# BatteryCombinerControlBoard.net
KiCad netlist of a schematic drawn in EAGLE
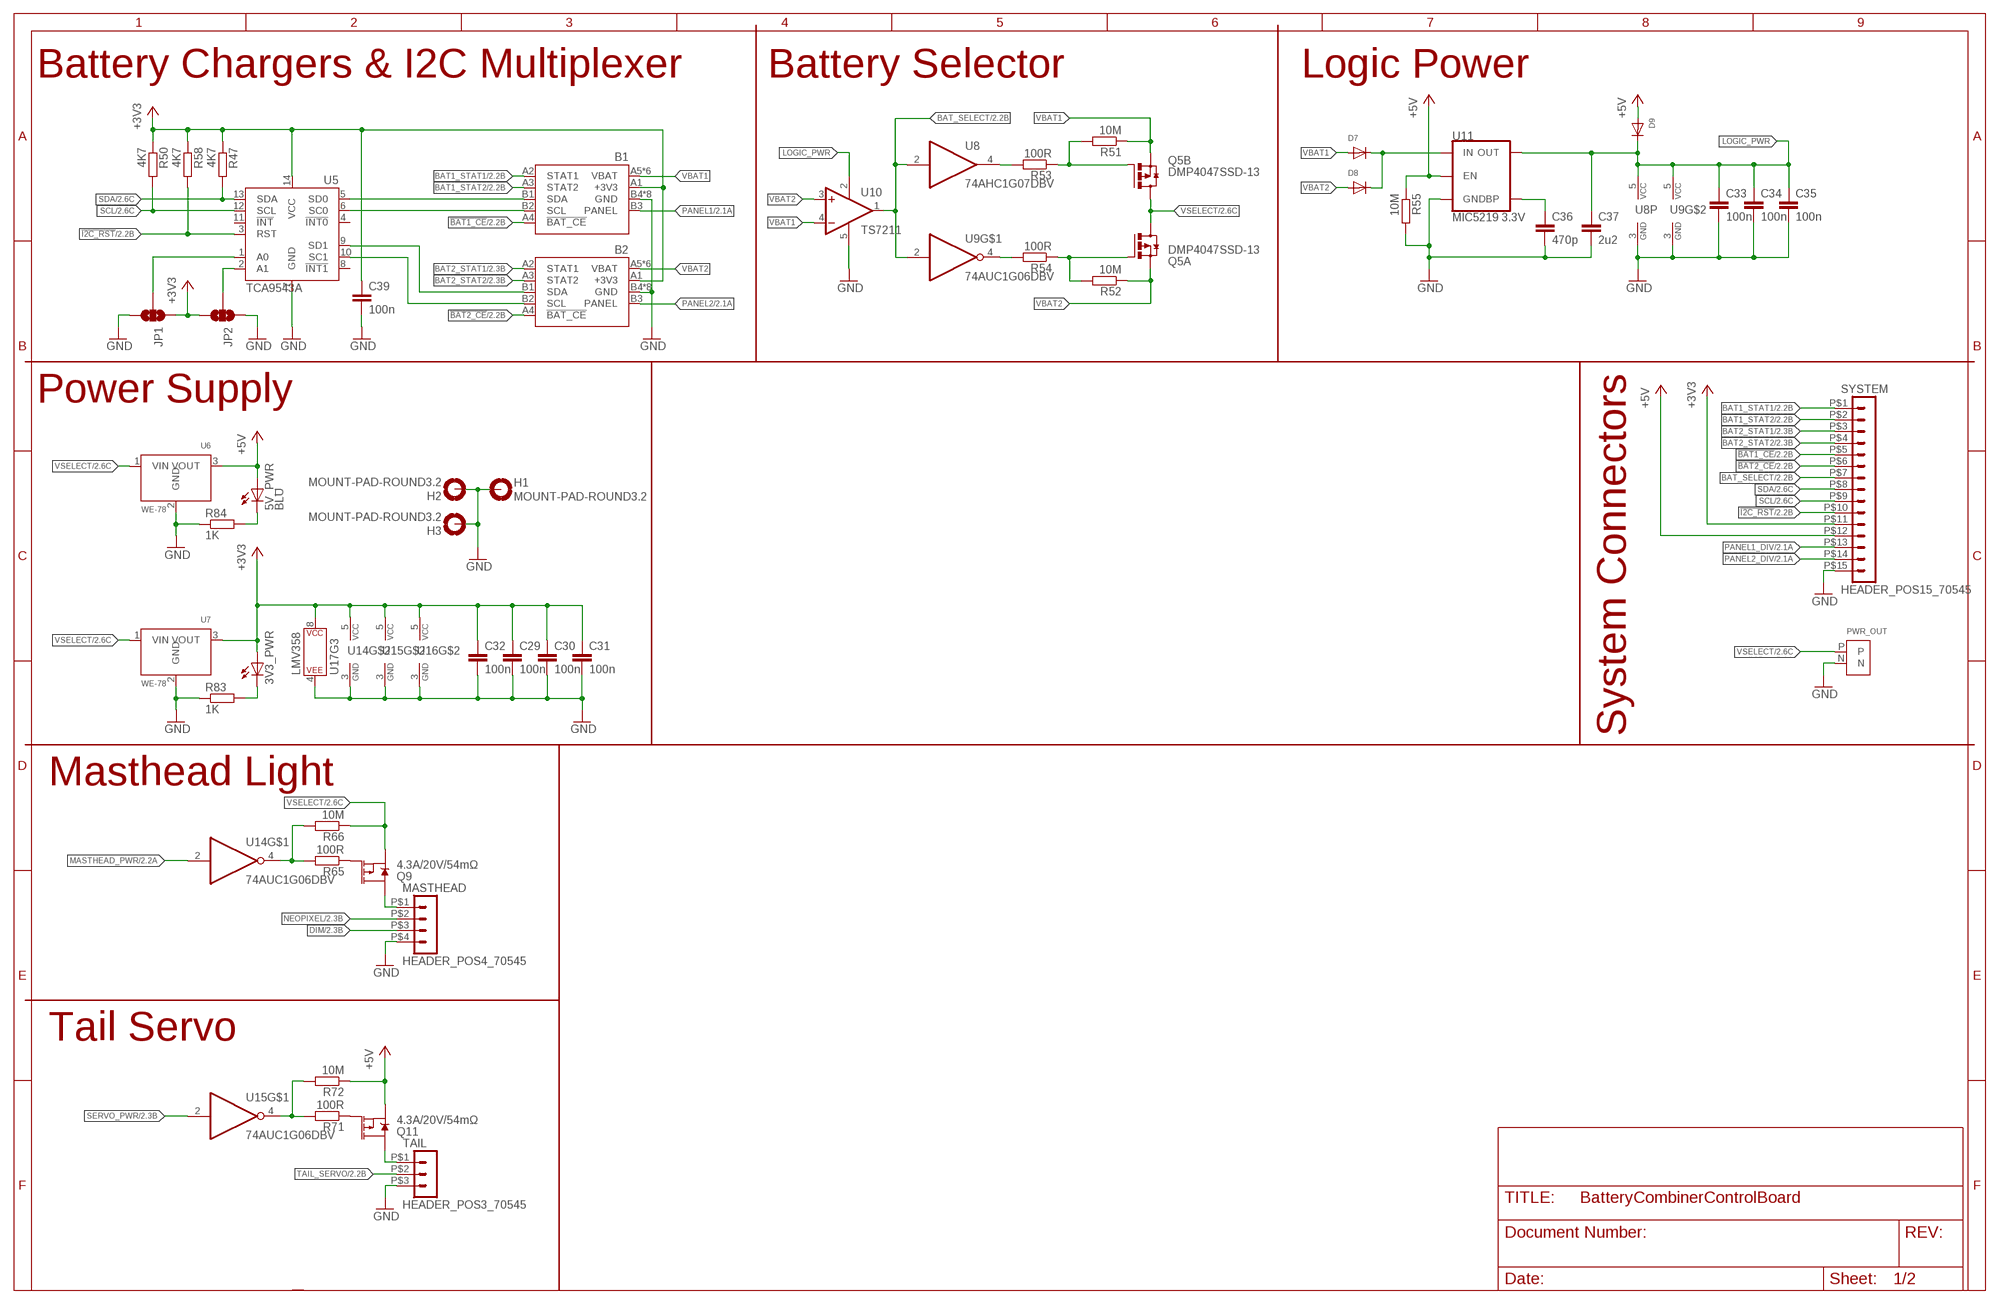
[diagram p0: schematic, sheet 1]
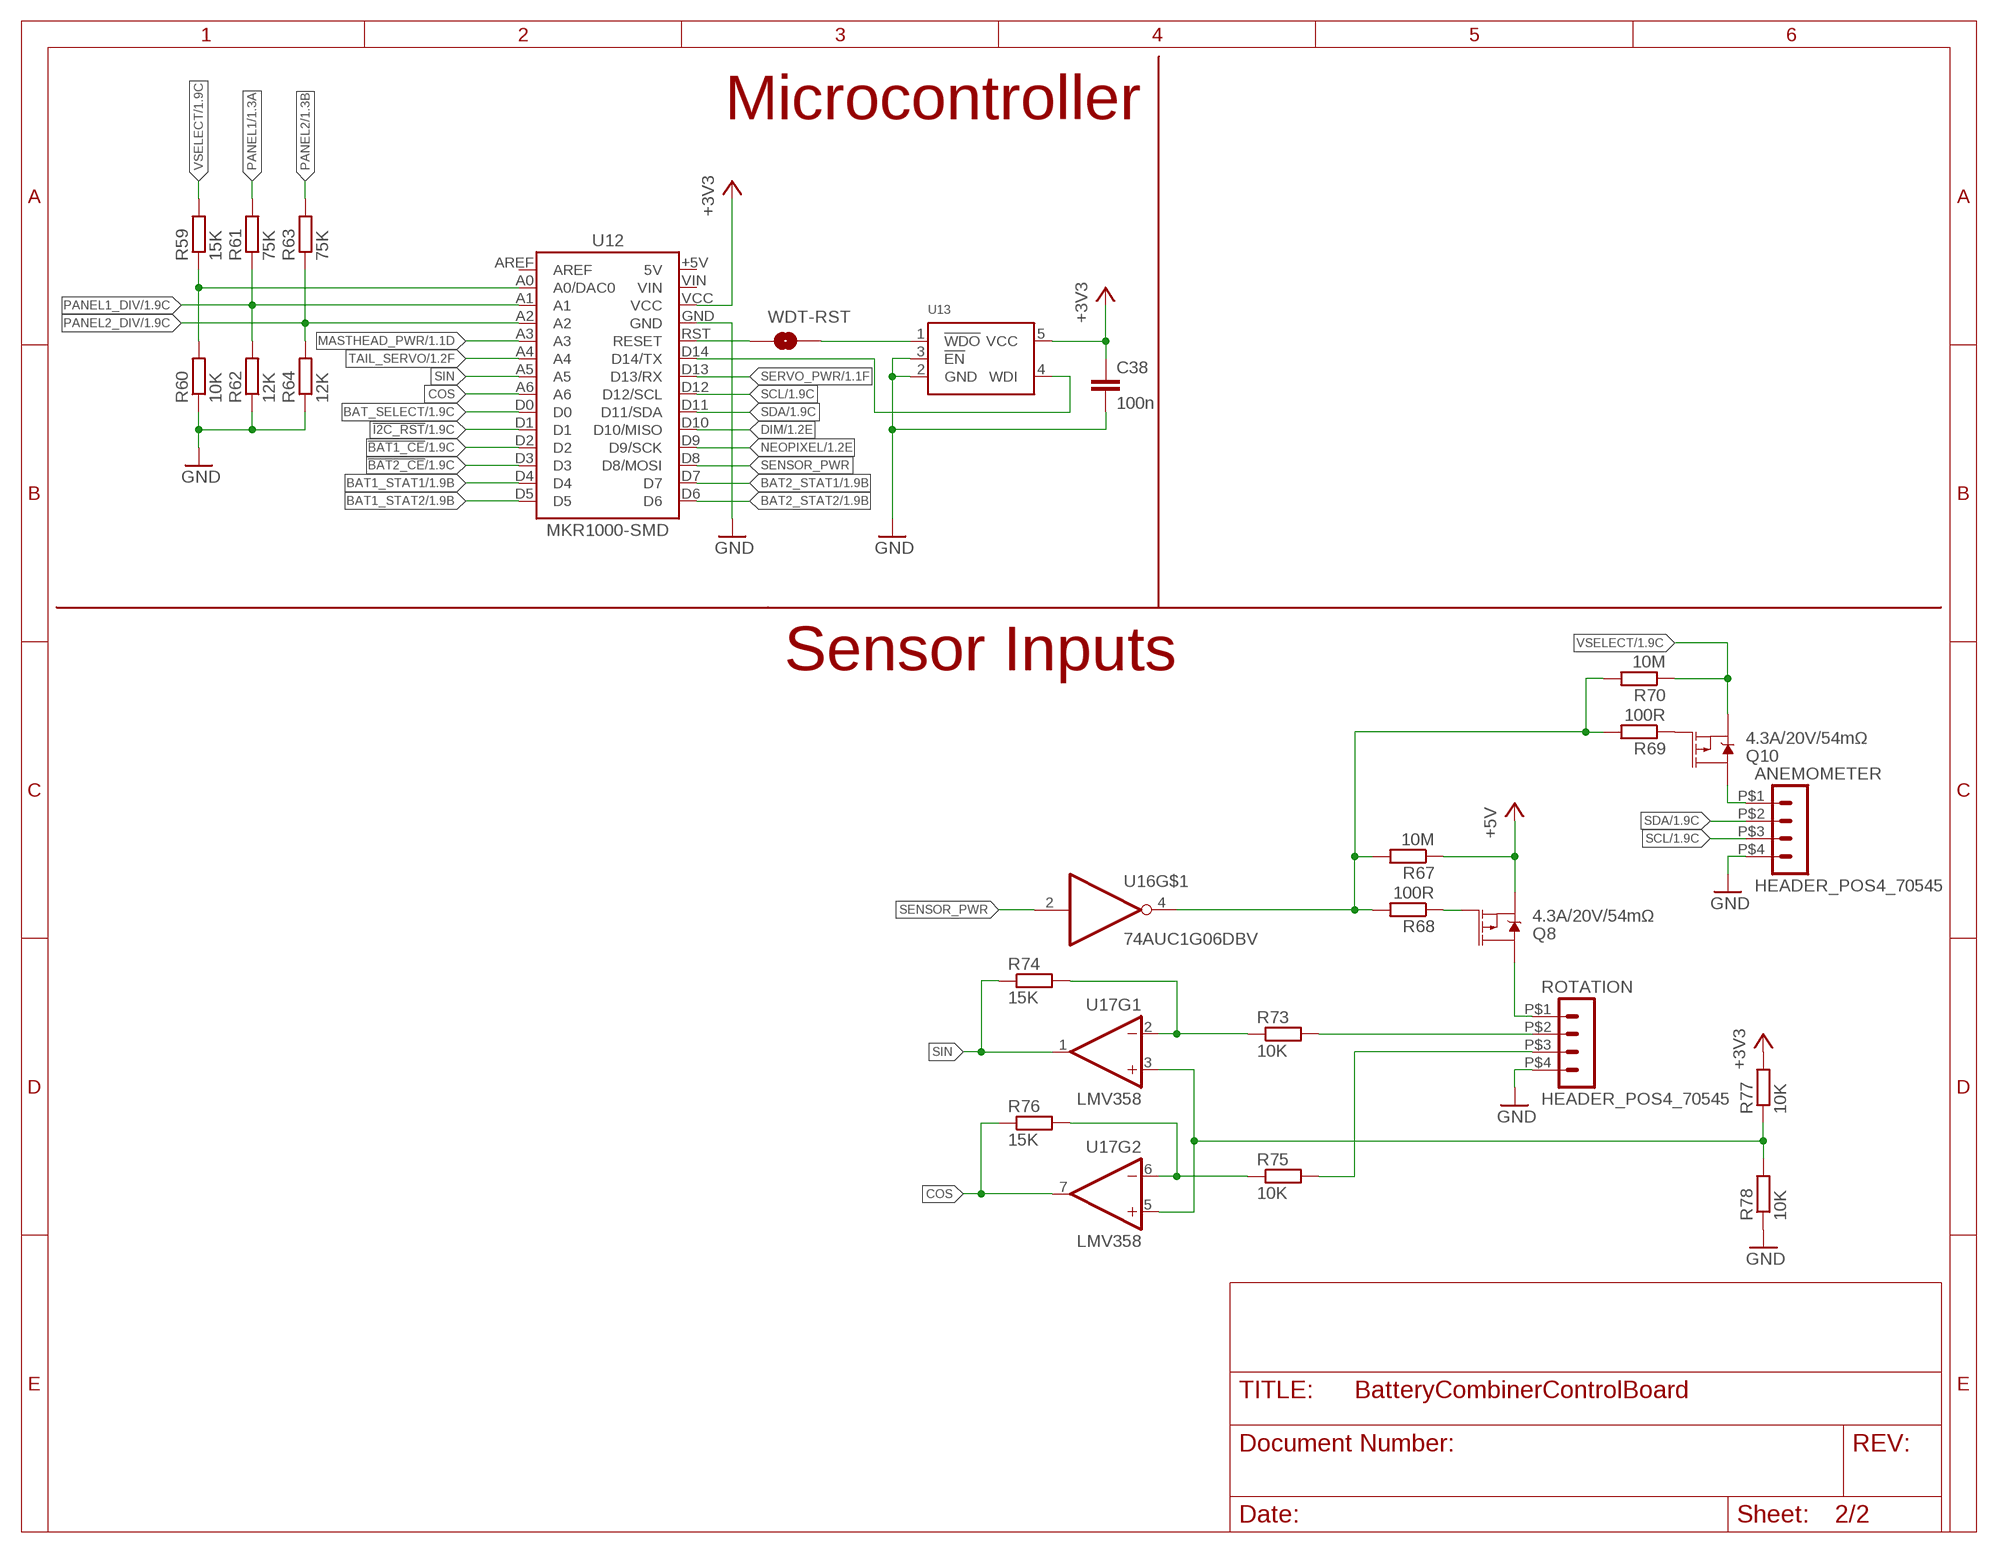
[diagram p1: schematic, sheet 2]

(export (version "E")
  (design (tool "Eeschema 10.0.6"))
  (components
    (comp (ref "ANEMOMETER")
      (value "HEADER_POS4_70545")
      (footprint "eagle-import:70545-POS4")
      (libsource (lib "eagle-import") (part "HEADER_POS4_?70545"))
    )
    (comp (ref "C38")
      (value "100n")
      (footprint "eagle-import:C0603")
      (libsource (lib "eagle-import") (part "C-EUC0603"))
    )
    (comp (ref "Q8")
      (value "4.3A/20V/54mΩ")
      (footprint "eagle-import:SOT23-3")
      (libsource (lib "eagle-import") (part "MOSFET_PCH-IRLML2244"))
    )
    (comp (ref "Q10")
      (value "4.3A/20V/54mΩ")
      (footprint "eagle-import:SOT23-3")
      (libsource (lib "eagle-import") (part "MOSFET_PCH-IRLML2244"))
    )
    (comp (ref "R59")
      (value "15K")
      (footprint "eagle-import:R0603")
      (libsource (lib "eagle-import") (part "R-EU_R0603"))
    )
    (comp (ref "R60")
      (value "10K")
      (footprint "eagle-import:R0603")
      (libsource (lib "eagle-import") (part "R-EU_R0603"))
    )
    (comp (ref "R61")
      (value "75K")
      (footprint "eagle-import:R0603")
      (libsource (lib "eagle-import") (part "R-EU_R0603"))
    )
    (comp (ref "R62")
      (value "12K")
      (footprint "eagle-import:R0603")
      (libsource (lib "eagle-import") (part "R-EU_R0603"))
    )
    (comp (ref "R63")
      (value "75K")
      (footprint "eagle-import:R0603")
      (libsource (lib "eagle-import") (part "R-EU_R0603"))
    )
    (comp (ref "R64")
      (value "12K")
      (footprint "eagle-import:R0603")
      (libsource (lib "eagle-import") (part "R-EU_R0603"))
    )
    (comp (ref "R67")
      (value "10M")
      (footprint "eagle-import:R0603")
      (libsource (lib "eagle-import") (part "R-EU_R0603"))
    )
    (comp (ref "R68")
      (value "100R")
      (footprint "eagle-import:R0603")
      (libsource (lib "eagle-import") (part "R-EU_R0603"))
    )
    (comp (ref "R69")
      (value "100R")
      (footprint "eagle-import:R0603")
      (libsource (lib "eagle-import") (part "R-EU_R0603"))
    )
    (comp (ref "R70")
      (value "10M")
      (footprint "eagle-import:R0603")
      (libsource (lib "eagle-import") (part "R-EU_R0603"))
    )
    (comp (ref "R73")
      (value "10K")
      (footprint "eagle-import:R0603")
      (libsource (lib "eagle-import") (part "R-EU_R0603"))
    )
    (comp (ref "R74")
      (value "15K")
      (footprint "eagle-import:R0603")
      (libsource (lib "eagle-import") (part "R-EU_R0603"))
    )
    (comp (ref "R75")
      (value "10K")
      (footprint "eagle-import:R0603")
      (libsource (lib "eagle-import") (part "R-EU_R0603"))
    )
    (comp (ref "R76")
      (value "15K")
      (footprint "eagle-import:R0603")
      (libsource (lib "eagle-import") (part "R-EU_R0603"))
    )
    (comp (ref "R77")
      (value "10K")
      (footprint "eagle-import:R0603")
      (libsource (lib "eagle-import") (part "R-EU_R0603"))
    )
    (comp (ref "R78")
      (value "10K")
      (footprint "eagle-import:R0603")
      (libsource (lib "eagle-import") (part "R-EU_R0603"))
    )
    (comp (ref "ROTATION")
      (value "HEADER_POS4_70545")
      (footprint "eagle-import:70545-POS4")
      (libsource (lib "eagle-import") (part "HEADER_POS4_?70545"))
    )
    (comp (ref "U12")
      (value "MKR1000-SMD")
      (footprint "eagle-import:MKR1000-SMD")
      (libsource (lib "eagle-import") (part "MKR1000-SMD"))
    )
    (comp (ref "U13")
      (value "STWD100")
      (footprint "eagle-import:DBV-R-PDSO-G5")
      (libsource (lib "eagle-import") (part "STWD100"))
    )
    (comp (ref "U16")
      (value "74AUC1G06DBV")
      (footprint "eagle-import:SOT23-5")
      (libsource (lib "eagle-import") (part "741G06DBVAUC"))
    )
    (comp (ref "U17")
      (value "LMV358")
      (footprint "eagle-import:SO08")
      (libsource (lib "eagle-import") (part "LMV358SOIC"))
    )
    (comp (ref "WDT-RST")
      (value "JUMPER-SMT_2_NO_SILK")
      (footprint "eagle-import:SMT-JUMPER_2_NO_SILK")
      (libsource (lib "eagle-import") (part "JUMPER-SMT_2_NO_SILK"))
    )
    (comp (ref "3V3_PWR")
      (value "GRN")
      (footprint "eagle-import:CHIP-LED0603")
      (libsource (lib "eagle-import") (part "LEDCHIP-LED0603"))
    )
    (comp (ref "5V_PWR")
      (value "BLU")
      (footprint "eagle-import:CHIP-LED0603")
      (libsource (lib "eagle-import") (part "LEDCHIP-LED0603"))
    )
    (comp (ref "B1")
      (value "MPPTCHARGER")
      (footprint "eagle-import:MPPTCHARGER")
      (libsource (lib "eagle-import") (part "MPPTCHARGER"))
    )
    (comp (ref "B2")
      (value "MPPTCHARGER")
      (footprint "eagle-import:MPPTCHARGER")
      (libsource (lib "eagle-import") (part "MPPTCHARGER"))
    )
    (comp (ref "C29")
      (value "100n")
      (footprint "eagle-import:C0603")
      (libsource (lib "eagle-import") (part "C-EUC0603"))
    )
    (comp (ref "C30")
      (value "100n")
      (footprint "eagle-import:C0603")
      (libsource (lib "eagle-import") (part "C-EUC0603"))
    )
    (comp (ref "C31")
      (value "100n")
      (footprint "eagle-import:C0603")
      (libsource (lib "eagle-import") (part "C-EUC0603"))
    )
    (comp (ref "C32")
      (value "100n")
      (footprint "eagle-import:C0603")
      (libsource (lib "eagle-import") (part "C-EUC0603"))
    )
    (comp (ref "C33")
      (value "100n")
      (footprint "eagle-import:C0603")
      (libsource (lib "eagle-import") (part "C-EUC0603"))
    )
    (comp (ref "C34")
      (value "100n")
      (footprint "eagle-import:C0603")
      (libsource (lib "eagle-import") (part "C-EUC0603"))
    )
    (comp (ref "C35")
      (value "100n")
      (footprint "eagle-import:C0603")
      (libsource (lib "eagle-import") (part "C-EUC0603"))
    )
    (comp (ref "C36")
      (value "470p")
      (footprint "eagle-import:C0603")
      (libsource (lib "eagle-import") (part "C-EUC0603"))
    )
    (comp (ref "C37")
      (value "2u2")
      (footprint "eagle-import:C0603")
      (libsource (lib "eagle-import") (part "C-EUC0603"))
    )
    (comp (ref "C39")
      (value "100n")
      (footprint "eagle-import:C0603")
      (libsource (lib "eagle-import") (part "C-EUC0603"))
    )
    (comp (ref "D7")
      (value "DIODESOD-123")
      (footprint "eagle-import:SOD-123")
      (libsource (lib "eagle-import") (part "DIODESOD-123"))
    )
    (comp (ref "D8")
      (value "DIODESOD-123")
      (footprint "eagle-import:SOD-123")
      (libsource (lib "eagle-import") (part "DIODESOD-123"))
    )
    (comp (ref "D9")
      (value "DIODESOD-123")
      (footprint "eagle-import:SOD-123")
      (libsource (lib "eagle-import") (part "DIODESOD-123"))
    )
    (comp (ref "H1")
      (value "MOUNT-PAD-ROUND3.2")
      (footprint "eagle-import:3,2-PAD")
      (libsource (lib "eagle-import") (part "MOUNT-PAD-ROUND3.2"))
    )
    (comp (ref "H2")
      (value "MOUNT-PAD-ROUND3.2")
      (footprint "eagle-import:3,2-PAD")
      (libsource (lib "eagle-import") (part "MOUNT-PAD-ROUND3.2"))
    )
    (comp (ref "H3")
      (value "MOUNT-PAD-ROUND3.2")
      (footprint "eagle-import:3,2-PAD")
      (libsource (lib "eagle-import") (part "MOUNT-PAD-ROUND3.2"))
    )
    (comp (ref "JP1")
      (value "JUMPER-SMT_3_NO_SILK")
      (footprint "eagle-import:SMT-JUMPER_3_NO_SILK")
      (libsource (lib "eagle-import") (part "JUMPER-SMT_3_NO_SILK"))
    )
    (comp (ref "JP2")
      (value "JUMPER-SMT_3_NO_SILK")
      (footprint "eagle-import:SMT-JUMPER_3_NO_SILK")
      (libsource (lib "eagle-import") (part "JUMPER-SMT_3_NO_SILK"))
    )
    (comp (ref "MASTHEAD")
      (value "HEADER_POS4_70545")
      (footprint "eagle-import:70545-POS4")
      (libsource (lib "eagle-import") (part "HEADER_POS4_?70545"))
    )
    (comp (ref "PWR_OUT")
      (value "PWR")
      (footprint "eagle-import:JST-XH2-THRUHOLE")
      (libsource (lib "eagle-import") (part "PWR"))
    )
    (comp (ref "Q5")
      (value "DMP4047SSD-13")
      (footprint "eagle-import:SO08")
      (libsource (lib "eagle-import") (part "DMP4047SSD-13"))
    )
    (comp (ref "Q9")
      (value "4.3A/20V/54mΩ")
      (footprint "eagle-import:SOT23-3")
      (libsource (lib "eagle-import") (part "MOSFET_PCH-IRLML2244"))
    )
    (comp (ref "Q11")
      (value "4.3A/20V/54mΩ")
      (footprint "eagle-import:SOT23-3")
      (libsource (lib "eagle-import") (part "MOSFET_PCH-IRLML2244"))
    )
    (comp (ref "R47")
      (value "4K7")
      (footprint "eagle-import:R0603")
      (libsource (lib "eagle-import") (part "R-EU_R0603"))
    )
    (comp (ref "R50")
      (value "4K7")
      (footprint "eagle-import:R0603")
      (libsource (lib "eagle-import") (part "R-EU_R0603"))
    )
    (comp (ref "R51")
      (value "10M")
      (footprint "eagle-import:R0603")
      (libsource (lib "eagle-import") (part "R-EU_R0603"))
    )
    (comp (ref "R52")
      (value "10M")
      (footprint "eagle-import:R0603")
      (libsource (lib "eagle-import") (part "R-EU_R0603"))
    )
    (comp (ref "R53")
      (value "100R")
      (footprint "eagle-import:R0603")
      (libsource (lib "eagle-import") (part "R-EU_R0603"))
    )
    (comp (ref "R54")
      (value "100R")
      (footprint "eagle-import:R0603")
      (libsource (lib "eagle-import") (part "R-EU_R0603"))
    )
    (comp (ref "R55")
      (value "10M")
      (footprint "eagle-import:R0603")
      (libsource (lib "eagle-import") (part "R-EU_R0603"))
    )
    (comp (ref "R58")
      (value "4K7")
      (footprint "eagle-import:R0603")
      (libsource (lib "eagle-import") (part "R-EU_R0603"))
    )
    (comp (ref "R65")
      (value "100R")
      (footprint "eagle-import:R0603")
      (libsource (lib "eagle-import") (part "R-EU_R0603"))
    )
    (comp (ref "R66")
      (value "10M")
      (footprint "eagle-import:R0603")
      (libsource (lib "eagle-import") (part "R-EU_R0603"))
    )
    (comp (ref "R71")
      (value "100R")
      (footprint "eagle-import:R0603")
      (libsource (lib "eagle-import") (part "R-EU_R0603"))
    )
    (comp (ref "R72")
      (value "10M")
      (footprint "eagle-import:R0603")
      (libsource (lib "eagle-import") (part "R-EU_R0603"))
    )
    (comp (ref "R83")
      (value "1K")
      (footprint "eagle-import:R0603")
      (libsource (lib "eagle-import") (part "R-EU_R0603"))
    )
    (comp (ref "R84")
      (value "1K")
      (footprint "eagle-import:R0603")
      (libsource (lib "eagle-import") (part "R-EU_R0603"))
    )
    (comp (ref "SYSTEM")
      (value "HEADER_POS15_70545")
      (footprint "eagle-import:70545-POS15")
      (libsource (lib "eagle-import") (part "HEADER_POS15_?70545"))
    )
    (comp (ref "TAIL")
      (value "HEADER_POS3_70545")
      (footprint "eagle-import:70545-POS3")
      (libsource (lib "eagle-import") (part "HEADER_POS3_?70545"))
    )
    (comp (ref "U5")
      (value "TCA9543A")
      (footprint "eagle-import:SO-14")
      (libsource (lib "eagle-import") (part "TCA9543A"))
    )
    (comp (ref "U6")
      (value "WE-78")
      (footprint "eagle-import:WE-78")
      (libsource (lib "eagle-import") (part "WE-78"))
    )
    (comp (ref "U7")
      (value "WE-78")
      (footprint "eagle-import:WE-78")
      (libsource (lib "eagle-import") (part "WE-78"))
    )
    (comp (ref "U8")
      (value "74AHC1G07DBV")
      (footprint "eagle-import:SOT23-5")
      (libsource (lib "eagle-import") (part "741G07DBVAHC"))
    )
    (comp (ref "U9")
      (value "74AUC1G06DBV")
      (footprint "eagle-import:SOT23-5")
      (libsource (lib "eagle-import") (part "741G06DBVAUC"))
    )
    (comp (ref "U10")
      (value "TS7211")
      (footprint "eagle-import:DBV-R-PDSO-G5")
      (libsource (lib "eagle-import") (part "TS7211"))
    )
    (comp (ref "U11")
      (value "MIC5219 3.3V")
      (footprint "eagle-import:SOT23-5")
      (libsource (lib "eagle-import") (part "V_REG_MIC52193.3V"))
    )
    (comp (ref "U14")
      (value "74AUC1G06DBV")
      (footprint "eagle-import:SOT23-5")
      (libsource (lib "eagle-import") (part "741G06DBVAUC"))
    )
    (comp (ref "U15")
      (value "74AUC1G06DBV")
      (footprint "eagle-import:SOT23-5")
      (libsource (lib "eagle-import") (part "741G06DBVAUC"))
    )
  )
  (nets
    (net (code "1") (name "+3V3") (class "Default")
      (node (ref "3V3_PWR") (pin "A") (pinfunction "A_A") (pintype "passive"))
      (node (ref "B1") (pin "A1") (pinfunction "+3V3_A1") (pintype "bidirectional"))
      (node (ref "B2") (pin "A1") (pinfunction "+3V3_A1") (pintype "bidirectional"))
      (node (ref "C29") (pin "1") (pinfunction "1_1") (pintype "passive"))
      (node (ref "C30") (pin "1") (pinfunction "1_1") (pintype "passive"))
      (node (ref "C31") (pin "1") (pinfunction "1_1") (pintype "passive"))
      (node (ref "C32") (pin "1") (pinfunction "1_1") (pintype "passive"))
      (node (ref "C38") (pin "1") (pinfunction "1_1") (pintype "passive"))
      (node (ref "C39") (pin "1") (pinfunction "1_1") (pintype "passive"))
      (node (ref "JP1") (pin "1") (pinfunction "1_1") (pintype "passive"))
      (node (ref "JP2") (pin "3") (pinfunction "3_3") (pintype "passive"))
      (node (ref "R47") (pin "1") (pinfunction "1_1") (pintype "passive"))
      (node (ref "R50") (pin "1") (pinfunction "1_1") (pintype "passive"))
      (node (ref "R58") (pin "1") (pinfunction "1_1") (pintype "passive"))
      (node (ref "R77") (pin "2") (pinfunction "2_2") (pintype "passive"))
      (node (ref "SYSTEM") (pin "P$11") (pinfunction "11_P$11") (pintype "passive"))
      (node (ref "U12") (pin "VCC") (pinfunction "VCC_VCC") (pintype "bidirectional"))
      (node (ref "U13") (pin "5") (pinfunction "VCC_5") (pintype "bidirectional"))
      (node (ref "U14") (pin "5") (pinfunction "VCC_5") (pintype "power_in"))
      (node (ref "U15") (pin "5") (pinfunction "VCC_5") (pintype "power_in"))
      (node (ref "U16") (pin "5") (pinfunction "VCC_5") (pintype "power_in"))
      (node (ref "U17") (pin "8") (pinfunction "P$V+_8") (pintype "bidirectional"))
      (node (ref "U5") (pin "14") (pinfunction "VCC_14") (pintype "bidirectional"))
      (node (ref "U7") (pin "3") (pinfunction "VOUT_3") (pintype "bidirectional"))
    )
    (net (code "2") (name "+5V") (class "Default")
      (node (ref "5V_PWR") (pin "A") (pinfunction "A_A") (pintype "passive"))
      (node (ref "D9") (pin "A") (pinfunction "A_A") (pintype "passive"))
      (node (ref "Q11") (pin "2") (pinfunction "S_2") (pintype "bidirectional"))
      (node (ref "Q8") (pin "2") (pinfunction "S_2") (pintype "bidirectional"))
      (node (ref "R55") (pin "1") (pinfunction "1_1") (pintype "passive"))
      (node (ref "R67") (pin "1") (pinfunction "1_1") (pintype "passive"))
      (node (ref "R72") (pin "1") (pinfunction "1_1") (pintype "passive"))
      (node (ref "SYSTEM") (pin "P$12") (pinfunction "12_P$12") (pintype "passive"))
      (node (ref "U11") (pin "3") (pinfunction "EN_3") (pintype "input"))
      (node (ref "U6") (pin "3") (pinfunction "VOUT_3") (pintype "bidirectional"))
    )
    (net (code "3") (name "BAT1_STAT1") (class "Default")
      (node (ref "B1") (pin "A2") (pinfunction "STAT1_A2") (pintype "bidirectional"))
      (node (ref "SYSTEM") (pin "P$1") (pinfunction "1_P$1") (pintype "passive"))
      (node (ref "U12") (pin "D4") (pinfunction "D4_D4") (pintype "bidirectional"))
    )
    (net (code "4") (name "BAT1_STAT2") (class "Default")
      (node (ref "B1") (pin "A3") (pinfunction "STAT2_A3") (pintype "bidirectional"))
      (node (ref "SYSTEM") (pin "P$2") (pinfunction "2_P$2") (pintype "passive"))
      (node (ref "U12") (pin "D5") (pinfunction "D5_D5") (pintype "bidirectional"))
    )
    (net (code "5") (name "BAT2_STAT1") (class "Default")
      (node (ref "B2") (pin "A2") (pinfunction "STAT1_A2") (pintype "bidirectional"))
      (node (ref "SYSTEM") (pin "P$3") (pinfunction "3_P$3") (pintype "passive"))
      (node (ref "U12") (pin "D7") (pinfunction "D7_D7") (pintype "bidirectional"))
    )
    (net (code "6") (name "BAT2_STAT2") (class "Default")
      (node (ref "B2") (pin "A3") (pinfunction "STAT2_A3") (pintype "bidirectional"))
      (node (ref "SYSTEM") (pin "P$4") (pinfunction "4_P$4") (pintype "passive"))
      (node (ref "U12") (pin "D6") (pinfunction "D6_D6") (pintype "bidirectional"))
    )
    (net (code "7") (name "BAT_SELECT") (class "Default")
      (node (ref "SYSTEM") (pin "P$7") (pinfunction "7_P$7") (pintype "passive"))
      (node (ref "U10") (pin "1") (pinfunction "OUT_1") (pintype "output"))
      (node (ref "U12") (pin "D0") (pinfunction "D0_D0") (pintype "bidirectional"))
      (node (ref "U8") (pin "2") (pinfunction "I_2") (pintype "input"))
      (node (ref "U9") (pin "2") (pinfunction "I_2") (pintype "input"))
    )
    (net (code "8") (name "COS") (class "Default")
      (node (ref "R76") (pin "1") (pinfunction "1_1") (pintype "passive"))
      (node (ref "U12") (pin "A6") (pinfunction "A6_A6") (pintype "bidirectional"))
      (node (ref "U17") (pin "7") (pinfunction "OUT_7") (pintype "output"))
    )
    (net (code "9") (name "DIM") (class "Default")
      (node (ref "MASTHEAD") (pin "P$3") (pinfunction "3_P$3") (pintype "passive"))
      (node (ref "U12") (pin "D10") (pinfunction "D10/MISO_D10") (pintype "bidirectional"))
    )
    (net (code "10") (name "GND") (class "Default")
      (node (ref "ANEMOMETER") (pin "P$4") (pinfunction "4_P$4") (pintype "passive"))
      (node (ref "B1") (pin "B10") (pinfunction "GND_B10") (pintype "bidirectional"))
      (node (ref "B1") (pin "B4") (pinfunction "GND_B4") (pintype "bidirectional"))
      (node (ref "B1") (pin "B5") (pinfunction "GND_B5") (pintype "bidirectional"))
      (node (ref "B1") (pin "B6") (pinfunction "GND_B6") (pintype "bidirectional"))
      (node (ref "B1") (pin "B7") (pinfunction "GND_B7") (pintype "bidirectional"))
      (node (ref "B1") (pin "B8") (pinfunction "GND_B8") (pintype "bidirectional"))
      (node (ref "B1") (pin "B9") (pinfunction "GND_B9") (pintype "bidirectional"))
      (node (ref "B1") (pin "H") (pinfunction "GND_H") (pintype "bidirectional"))
      (node (ref "B2") (pin "B10") (pinfunction "GND_B10") (pintype "bidirectional"))
      (node (ref "B2") (pin "B4") (pinfunction "GND_B4") (pintype "bidirectional"))
      (node (ref "B2") (pin "B5") (pinfunction "GND_B5") (pintype "bidirectional"))
      (node (ref "B2") (pin "B6") (pinfunction "GND_B6") (pintype "bidirectional"))
      (node (ref "B2") (pin "B7") (pinfunction "GND_B7") (pintype "bidirectional"))
      (node (ref "B2") (pin "B8") (pinfunction "GND_B8") (pintype "bidirectional"))
      (node (ref "B2") (pin "B9") (pinfunction "GND_B9") (pintype "bidirectional"))
      (node (ref "B2") (pin "H") (pinfunction "GND_H") (pintype "bidirectional"))
      (node (ref "C29") (pin "2") (pinfunction "2_2") (pintype "passive"))
      (node (ref "C30") (pin "2") (pinfunction "2_2") (pintype "passive"))
      (node (ref "C31") (pin "2") (pinfunction "2_2") (pintype "passive"))
      (node (ref "C32") (pin "2") (pinfunction "2_2") (pintype "passive"))
      (node (ref "C33") (pin "2") (pinfunction "2_2") (pintype "passive"))
      (node (ref "C34") (pin "2") (pinfunction "2_2") (pintype "passive"))
      (node (ref "C35") (pin "2") (pinfunction "2_2") (pintype "passive"))
      (node (ref "C36") (pin "2") (pinfunction "2_2") (pintype "passive"))
      (node (ref "C37") (pin "2") (pinfunction "2_2") (pintype "passive"))
      (node (ref "C38") (pin "2") (pinfunction "2_2") (pintype "passive"))
      (node (ref "C39") (pin "2") (pinfunction "2_2") (pintype "passive"))
      (node (ref "H1") (pin "B3,2") (pinfunction "MOUNT_B3,2") (pintype "passive"))
      (node (ref "H2") (pin "B3,2") (pinfunction "MOUNT_B3,2") (pintype "passive"))
      (node (ref "H3") (pin "B3,2") (pinfunction "MOUNT_B3,2") (pintype "passive"))
      (node (ref "JP1") (pin "3") (pinfunction "3_3") (pintype "passive"))
      (node (ref "JP2") (pin "1") (pinfunction "1_1") (pintype "passive"))
      (node (ref "MASTHEAD") (pin "P$4") (pinfunction "4_P$4") (pintype "passive"))
      (node (ref "PWR_OUT") (pin "N") (pinfunction "N_N") (pintype "bidirectional"))
      (node (ref "R55") (pin "2") (pinfunction "2_2") (pintype "passive"))
      (node (ref "R60") (pin "1") (pinfunction "1_1") (pintype "passive"))
      (node (ref "R62") (pin "1") (pinfunction "1_1") (pintype "passive"))
      (node (ref "R64") (pin "1") (pinfunction "1_1") (pintype "passive"))
      (node (ref "R78") (pin "1") (pinfunction "1_1") (pintype "passive"))
      (node (ref "R83") (pin "1") (pinfunction "1_1") (pintype "passive"))
      (node (ref "R84") (pin "1") (pinfunction "1_1") (pintype "passive"))
      (node (ref "ROTATION") (pin "P$4") (pinfunction "4_P$4") (pintype "passive"))
      (node (ref "SYSTEM") (pin "P$15") (pinfunction "15_P$15") (pintype "passive"))
      (node (ref "TAIL") (pin "P$3") (pinfunction "3_P$3") (pintype "passive"))
      (node (ref "U10") (pin "5") (pinfunction "GND_5") (pintype "power_in"))
      (node (ref "U11") (pin "2") (pinfunction "GND_2") (pintype "input"))
      (node (ref "U12") (pin "GND") (pinfunction "GND_GND") (pintype "bidirectional"))
      (node (ref "U13") (pin "2") (pinfunction "GND_2") (pintype "bidirectional"))
      (node (ref "U13") (pin "3") (pinfunction "~{EN}_3") (pintype "bidirectional"))
      (node (ref "U14") (pin "3") (pinfunction "GND_3") (pintype "power_in"))
      (node (ref "U15") (pin "3") (pinfunction "GND_3") (pintype "power_in"))
      (node (ref "U16") (pin "3") (pinfunction "GND_3") (pintype "power_in"))
      (node (ref "U17") (pin "4") (pinfunction "P$V-_4") (pintype "bidirectional"))
      (node (ref "U5") (pin "7") (pinfunction "GND_7") (pintype "bidirectional"))
      (node (ref "U6") (pin "2") (pinfunction "GND_2") (pintype "bidirectional"))
      (node (ref "U7") (pin "2") (pinfunction "GND_2") (pintype "bidirectional"))
      (node (ref "U8") (pin "3") (pinfunction "GND_3") (pintype "power_in"))
      (node (ref "U9") (pin "3") (pinfunction "GND_3") (pintype "power_in"))
    )
    (net (code "11") (name "LOGIC_PWR") (class "Default")
      (node (ref "C33") (pin "1") (pinfunction "1_1") (pintype "passive"))
      (node (ref "C34") (pin "1") (pinfunction "1_1") (pintype "passive"))
      (node (ref "C35") (pin "1") (pinfunction "1_1") (pintype "passive"))
      (node (ref "C37") (pin "1") (pinfunction "1_1") (pintype "passive"))
      (node (ref "D9") (pin "C") (pinfunction "C_C") (pintype "passive"))
      (node (ref "U10") (pin "2") (pinfunction "V+_2") (pintype "power_in"))
      (node (ref "U11") (pin "5") (pinfunction "OUT_5") (pintype "passive"))
      (node (ref "U8") (pin "5") (pinfunction "VCC_5") (pintype "power_in"))
      (node (ref "U9") (pin "5") (pinfunction "VCC_5") (pintype "power_in"))
    )
    (net (code "12") (name "MASTHEAD_PWR") (class "Default")
      (node (ref "U12") (pin "A3") (pinfunction "A3_A3") (pintype "bidirectional"))
      (node (ref "U14") (pin "2") (pinfunction "I_2") (pintype "input"))
    )
    (net (code "13") (name "NEOPIXEL") (class "Default")
      (node (ref "MASTHEAD") (pin "P$2") (pinfunction "2_P$2") (pintype "passive"))
      (node (ref "U12") (pin "D9") (pinfunction "D9/SCK_D9") (pintype "bidirectional"))
    )
    (net (code "14") (name "Net-(3V3_PWR-PadC)") (class "Default")
      (node (ref "3V3_PWR") (pin "C") (pinfunction "C_C") (pintype "passive"))
      (node (ref "R83") (pin "2") (pinfunction "2_2") (pintype "passive"))
    )
    (net (code "15") (name "Net-(5V_PWR-PadC)") (class "Default")
      (node (ref "5V_PWR") (pin "C") (pinfunction "C_C") (pintype "passive"))
      (node (ref "R84") (pin "2") (pinfunction "2_2") (pintype "passive"))
    )
    (net (code "16") (name "Net-(ANEMOMETER-1)") (class "Default")
      (node (ref "ANEMOMETER") (pin "P$1") (pinfunction "1_P$1") (pintype "passive"))
      (node (ref "Q10") (pin "3") (pinfunction "D_3") (pintype "bidirectional"))
    )
    (net (code "17") (name "Net-(B1-SCL)") (class "Default")
      (node (ref "B1") (pin "B2") (pinfunction "SCL_B2") (pintype "bidirectional"))
      (node (ref "U5") (pin "6") (pinfunction "SC0_6") (pintype "bidirectional"))
    )
    (net (code "18") (name "Net-(B1-SDA)") (class "Default")
      (node (ref "B1") (pin "B1") (pinfunction "SDA_B1") (pintype "bidirectional"))
      (node (ref "U5") (pin "5") (pinfunction "SD0_5") (pintype "bidirectional"))
    )
    (net (code "19") (name "Net-(B2-SCL)") (class "Default")
      (node (ref "B2") (pin "B2") (pinfunction "SCL_B2") (pintype "bidirectional"))
      (node (ref "U5") (pin "10") (pinfunction "SC1_10") (pintype "bidirectional"))
    )
    (net (code "20") (name "Net-(B2-SDA)") (class "Default")
      (node (ref "B2") (pin "B1") (pinfunction "SDA_B1") (pintype "bidirectional"))
      (node (ref "U5") (pin "9") (pinfunction "SD1_9") (pintype "bidirectional"))
    )
    (net (code "21") (name "Net-(MASTHEAD-1)") (class "Default")
      (node (ref "MASTHEAD") (pin "P$1") (pinfunction "1_P$1") (pintype "passive"))
      (node (ref "Q9") (pin "3") (pinfunction "D_3") (pintype "bidirectional"))
    )
    (net (code "22") (name "Net-(Q5A-G)") (class "Default")
      (node (ref "Q5") (pin "2") (pinfunction "G_2") (pintype "passive"))
      (node (ref "R52") (pin "2") (pinfunction "2_2") (pintype "passive"))
      (node (ref "R54") (pin "1") (pinfunction "1_1") (pintype "passive"))
    )
    (net (code "23") (name "Net-(Q5B-G)") (class "Default")
      (node (ref "Q5") (pin "4") (pinfunction "G_4") (pintype "passive"))
      (node (ref "R51") (pin "2") (pinfunction "2_2") (pintype "passive"))
      (node (ref "R53") (pin "1") (pinfunction "1_1") (pintype "passive"))
    )
    (net (code "24") (name "Net-(Q8-D)") (class "Default")
      (node (ref "Q8") (pin "3") (pinfunction "D_3") (pintype "bidirectional"))
      (node (ref "ROTATION") (pin "P$1") (pinfunction "1_P$1") (pintype "passive"))
    )
    (net (code "25") (name "Net-(Q8-G)") (class "Default")
      (node (ref "Q8") (pin "1") (pinfunction "G_1") (pintype "bidirectional"))
      (node (ref "R68") (pin "1") (pinfunction "1_1") (pintype "passive"))
    )
    (net (code "26") (name "Net-(Q9-G)") (class "Default")
      (node (ref "Q9") (pin "1") (pinfunction "G_1") (pintype "bidirectional"))
      (node (ref "R65") (pin "1") (pinfunction "1_1") (pintype "passive"))
    )
    (net (code "27") (name "Net-(Q10-G)") (class "Default")
      (node (ref "Q10") (pin "1") (pinfunction "G_1") (pintype "bidirectional"))
      (node (ref "R69") (pin "1") (pinfunction "1_1") (pintype "passive"))
    )
    (net (code "28") (name "Net-(Q11-D)") (class "Default")
      (node (ref "Q11") (pin "3") (pinfunction "D_3") (pintype "bidirectional"))
      (node (ref "TAIL") (pin "P$1") (pinfunction "1_P$1") (pintype "passive"))
    )
    (net (code "29") (name "Net-(Q11-G)") (class "Default")
      (node (ref "Q11") (pin "1") (pinfunction "G_1") (pintype "bidirectional"))
      (node (ref "R71") (pin "1") (pinfunction "1_1") (pintype "passive"))
    )
    (net (code "30") (name "Net-(ROTATION-2)") (class "Default")
      (node (ref "R73") (pin "2") (pinfunction "2_2") (pintype "passive"))
      (node (ref "ROTATION") (pin "P$2") (pinfunction "2_P$2") (pintype "passive"))
    )
    (net (code "31") (name "Net-(ROTATION-3)") (class "Default")
      (node (ref "R75") (pin "2") (pinfunction "2_2") (pintype "passive"))
      (node (ref "ROTATION") (pin "P$3") (pinfunction "3_P$3") (pintype "passive"))
    )
    (net (code "32") (name "Net-(U5-A0)") (class "Default")
      (node (ref "JP1") (pin "2") (pinfunction "2_2") (pintype "passive"))
      (node (ref "U5") (pin "1") (pinfunction "A0_1") (pintype "bidirectional"))
    )
    (net (code "33") (name "Net-(U5-A1)") (class "Default")
      (node (ref "JP2") (pin "2") (pinfunction "2_2") (pintype "passive"))
      (node (ref "U5") (pin "2") (pinfunction "A1_2") (pintype "bidirectional"))
    )
    (net (code "34") (name "Net-(U8A-O)") (class "Default")
      (node (ref "R53") (pin "2") (pinfunction "2_2") (pintype "passive"))
      (node (ref "U8") (pin "4") (pinfunction "O_4") (pintype "open_collector"))
    )
    (net (code "35") (name "Net-(U9A-O)") (class "Default")
      (node (ref "R54") (pin "2") (pinfunction "2_2") (pintype "passive"))
      (node (ref "U9") (pin "4") (pinfunction "O_4") (pintype "open_collector"))
    )
    (net (code "36") (name "Net-(U11-BP)") (class "Default")
      (node (ref "C36") (pin "1") (pinfunction "1_1") (pintype "passive"))
      (node (ref "U11") (pin "4") (pinfunction "BP_4") (pintype "input"))
    )
    (net (code "37") (name "Net-(U11-IN)") (class "Default")
      (node (ref "D7") (pin "C") (pinfunction "C_C") (pintype "passive"))
      (node (ref "D8") (pin "C") (pinfunction "C_C") (pintype "passive"))
      (node (ref "U11") (pin "1") (pinfunction "IN_1") (pintype "input"))
    )
    (net (code "38") (name "Net-(U12-A0{slash}DAC0)") (class "Default")
      (node (ref "R59") (pin "1") (pinfunction "1_1") (pintype "passive"))
      (node (ref "R60") (pin "2") (pinfunction "2_2") (pintype "passive"))
      (node (ref "U12") (pin "A0") (pinfunction "A0/DAC0_A0") (pintype "bidirectional"))
    )
    (net (code "39") (name "Net-(U12-D14{slash}TX)") (class "Default")
      (node (ref "U12") (pin "D14") (pinfunction "D14/TX_D14") (pintype "bidirectional"))
      (node (ref "U13") (pin "4") (pinfunction "WDI_4") (pintype "bidirectional"))
    )
    (net (code "40") (name "Net-(U12-RESET)") (class "Default")
      (node (ref "U12") (pin "RST") (pinfunction "RESET_RST") (pintype "bidirectional"))
      (node (ref "WDT-RST") (pin "1") (pinfunction "1_1") (pintype "passive"))
    )
    (net (code "41") (name "Net-(U13-~{WDO})") (class "Default")
      (node (ref "U13") (pin "1") (pinfunction "~{WDO}_1") (pintype "bidirectional"))
      (node (ref "WDT-RST") (pin "2") (pinfunction "2_2") (pintype "passive"))
    )
    (net (code "42") (name "Net-(U14A-O)") (class "Default")
      (node (ref "R65") (pin "2") (pinfunction "2_2") (pintype "passive"))
      (node (ref "R66") (pin "2") (pinfunction "2_2") (pintype "passive"))
      (node (ref "U14") (pin "4") (pinfunction "O_4") (pintype "open_collector"))
    )
    (net (code "43") (name "Net-(U15A-O)") (class "Default")
      (node (ref "R71") (pin "2") (pinfunction "2_2") (pintype "passive"))
      (node (ref "R72") (pin "2") (pinfunction "2_2") (pintype "passive"))
      (node (ref "U15") (pin "4") (pinfunction "O_4") (pintype "open_collector"))
    )
    (net (code "44") (name "Net-(U16A-O)") (class "Default")
      (node (ref "R67") (pin "2") (pinfunction "2_2") (pintype "passive"))
      (node (ref "R68") (pin "2") (pinfunction "2_2") (pintype "passive"))
      (node (ref "R69") (pin "2") (pinfunction "2_2") (pintype "passive"))
      (node (ref "R70") (pin "2") (pinfunction "2_2") (pintype "passive"))
      (node (ref "U16") (pin "4") (pinfunction "O_4") (pintype "open_collector"))
    )
    (net (code "45") (name "Net-(U17A-+IN)") (class "Default")
      (node (ref "R77") (pin "1") (pinfunction "1_1") (pintype "passive"))
      (node (ref "R78") (pin "2") (pinfunction "2_2") (pintype "passive"))
      (node (ref "U17") (pin "3") (pinfunction "+IN_3") (pintype "input"))
      (node (ref "U17") (pin "5") (pinfunction "+IN_5") (pintype "input"))
    )
    (net (code "46") (name "Net-(U17A--IN)") (class "Default")
      (node (ref "R73") (pin "1") (pinfunction "1_1") (pintype "passive"))
      (node (ref "R74") (pin "2") (pinfunction "2_2") (pintype "passive"))
      (node (ref "U17") (pin "2") (pinfunction "-IN_2") (pintype "input"))
    )
    (net (code "47") (name "Net-(U17B--IN)") (class "Default")
      (node (ref "R75") (pin "1") (pinfunction "1_1") (pintype "passive"))
      (node (ref "R76") (pin "2") (pinfunction "2_2") (pintype "passive"))
      (node (ref "U17") (pin "6") (pinfunction "-IN_6") (pintype "input"))
    )
    (net (code "48") (name "PANEL1") (class "Default")
      (node (ref "B1") (pin "B3") (pinfunction "PANEL_B3") (pintype "bidirectional"))
      (node (ref "R61") (pin "2") (pinfunction "2_2") (pintype "passive"))
    )
    (net (code "49") (name "PANEL1_DIV") (class "Default")
      (node (ref "R61") (pin "1") (pinfunction "1_1") (pintype "passive"))
      (node (ref "R62") (pin "2") (pinfunction "2_2") (pintype "passive"))
      (node (ref "SYSTEM") (pin "P$13") (pinfunction "13_P$13") (pintype "passive"))
      (node (ref "U12") (pin "A1") (pinfunction "A1_A1") (pintype "bidirectional"))
    )
    (net (code "50") (name "PANEL2") (class "Default")
      (node (ref "B2") (pin "B3") (pinfunction "PANEL_B3") (pintype "bidirectional"))
      (node (ref "R63") (pin "2") (pinfunction "2_2") (pintype "passive"))
    )
    (net (code "51") (name "PANEL2_DIV") (class "Default")
      (node (ref "R63") (pin "1") (pinfunction "1_1") (pintype "passive"))
      (node (ref "R64") (pin "2") (pinfunction "2_2") (pintype "passive"))
      (node (ref "SYSTEM") (pin "P$14") (pinfunction "14_P$14") (pintype "passive"))
      (node (ref "U12") (pin "A2") (pinfunction "A2_A2") (pintype "bidirectional"))
    )
    (net (code "52") (name "SCL") (class "Default")
      (node (ref "ANEMOMETER") (pin "P$3") (pinfunction "3_P$3") (pintype "passive"))
      (node (ref "R50") (pin "2") (pinfunction "2_2") (pintype "passive"))
      (node (ref "SYSTEM") (pin "P$9") (pinfunction "9_P$9") (pintype "passive"))
      (node (ref "U12") (pin "D12") (pinfunction "D12/SCL_D12") (pintype "bidirectional"))
      (node (ref "U5") (pin "12") (pinfunction "SCL_12") (pintype "bidirectional"))
    )
    (net (code "53") (name "SDA") (class "Default")
      (node (ref "ANEMOMETER") (pin "P$2") (pinfunction "2_P$2") (pintype "passive"))
      (node (ref "R47") (pin "2") (pinfunction "2_2") (pintype "passive"))
      (node (ref "SYSTEM") (pin "P$8") (pinfunction "8_P$8") (pintype "passive"))
      (node (ref "U12") (pin "D11") (pinfunction "D11/SDA_D11") (pintype "bidirectional"))
      (node (ref "U5") (pin "13") (pinfunction "SDA_13") (pintype "bidirectional"))
    )
    (net (code "54") (name "SENSOR_PWR") (class "Default")
      (node (ref "U12") (pin "D8") (pinfunction "D8/MOSI_D8") (pintype "bidirectional"))
      (node (ref "U16") (pin "2") (pinfunction "I_2") (pintype "input"))
    )
    (net (code "55") (name "SERVO_PWR") (class "Default")
      (node (ref "U12") (pin "D13") (pinfunction "D13/RX_D13") (pintype "bidirectional"))
      (node (ref "U15") (pin "2") (pinfunction "I_2") (pintype "input"))
    )
    (net (code "56") (name "SIN") (class "Default")
      (node (ref "R74") (pin "1") (pinfunction "1_1") (pintype "passive"))
      (node (ref "U12") (pin "A5") (pinfunction "A5_A5") (pintype "bidirectional"))
      (node (ref "U17") (pin "1") (pinfunction "OUT_1") (pintype "output"))
    )
    (net (code "57") (name "TAIL_SERVO") (class "Default")
      (node (ref "TAIL") (pin "P$2") (pinfunction "2_P$2") (pintype "passive"))
      (node (ref "U12") (pin "A4") (pinfunction "A4_A4") (pintype "bidirectional"))
    )
    (net (code "58") (name "VBAT1") (class "Default")
      (node (ref "B1") (pin "A10") (pinfunction "VBAT_A10") (pintype "bidirectional"))
      (node (ref "B1") (pin "A5") (pinfunction "VBAT_A5") (pintype "bidirectional"))
      (node (ref "B1") (pin "A6") (pinfunction "VBAT_A6") (pintype "bidirectional"))
      (node (ref "B1") (pin "A7") (pinfunction "VBAT_A7") (pintype "bidirectional"))
      (node (ref "B1") (pin "A8") (pinfunction "VBAT_A8") (pintype "bidirectional"))
      (node (ref "B1") (pin "A9") (pinfunction "VBAT_A9") (pintype "bidirectional"))
      (node (ref "D7") (pin "A") (pinfunction "A_A") (pintype "passive"))
      (node (ref "Q5") (pin "3") (pinfunction "S_3") (pintype "passive"))
      (node (ref "R51") (pin "1") (pinfunction "1_1") (pintype "passive"))
      (node (ref "U10") (pin "4") (pinfunction "-IN_4") (pintype "input"))
    )
    (net (code "59") (name "VBAT2") (class "Default")
      (node (ref "B2") (pin "A10") (pinfunction "VBAT_A10") (pintype "bidirectional"))
      (node (ref "B2") (pin "A5") (pinfunction "VBAT_A5") (pintype "bidirectional"))
      (node (ref "B2") (pin "A6") (pinfunction "VBAT_A6") (pintype "bidirectional"))
      (node (ref "B2") (pin "A7") (pinfunction "VBAT_A7") (pintype "bidirectional"))
      (node (ref "B2") (pin "A8") (pinfunction "VBAT_A8") (pintype "bidirectional"))
      (node (ref "B2") (pin "A9") (pinfunction "VBAT_A9") (pintype "bidirectional"))
      (node (ref "D8") (pin "A") (pinfunction "A_A") (pintype "passive"))
      (node (ref "Q5") (pin "1") (pinfunction "S_1") (pintype "passive"))
      (node (ref "R52") (pin "1") (pinfunction "1_1") (pintype "passive"))
      (node (ref "U10") (pin "3") (pinfunction "+IN_3") (pintype "input"))
    )
    (net (code "60") (name "VSELECT") (class "Default")
      (node (ref "PWR_OUT") (pin "P") (pinfunction "P_P") (pintype "bidirectional"))
      (node (ref "Q10") (pin "2") (pinfunction "S_2") (pintype "bidirectional"))
      (node (ref "Q5") (pin "5") (pinfunction "D_5") (pintype "passive"))
      (node (ref "Q5") (pin "6") (pinfunction "D_6") (pintype "passive"))
      (node (ref "Q5") (pin "7") (pinfunction "D_7") (pintype "passive"))
      (node (ref "Q5") (pin "8") (pinfunction "D_8") (pintype "passive"))
      (node (ref "Q9") (pin "2") (pinfunction "S_2") (pintype "bidirectional"))
      (node (ref "R59") (pin "2") (pinfunction "2_2") (pintype "passive"))
      (node (ref "R66") (pin "1") (pinfunction "1_1") (pintype "passive"))
      (node (ref "R70") (pin "1") (pinfunction "1_1") (pintype "passive"))
      (node (ref "U6") (pin "1") (pinfunction "VIN_1") (pintype "bidirectional"))
      (node (ref "U7") (pin "1") (pinfunction "VIN_1") (pintype "bidirectional"))
    )
    (net (code "61") (name "unconnected-(U5-~{INT0}-Pad4)") (class "Default")
      (node (ref "U5") (pin "4") (pinfunction "~{INT0}_4") (pintype "bidirectional"))
    )
    (net (code "62") (name "unconnected-(U5-~{INT1}-Pad8)") (class "Default")
      (node (ref "U5") (pin "8") (pinfunction "~{INT1}_8") (pintype "bidirectional"))
    )
    (net (code "63") (name "unconnected-(U5-~{INT}-Pad11)") (class "Default")
      (node (ref "U5") (pin "11") (pinfunction "~{INT}_11") (pintype "bidirectional"))
    )
    (net (code "64") (name "unconnected-(U12-5V-Pad+5V)") (class "Default")
      (node (ref "U12") (pin "+5V") (pinfunction "5V_+5V") (pintype "bidirectional"))
    )
    (net (code "65") (name "unconnected-(U12-PadAREF)") (class "Default")
      (node (ref "U12") (pin "AREF") (pinfunction "AREF_AREF") (pintype "bidirectional"))
    )
    (net (code "66") (name "unconnected-(U12-PadVIN)") (class "Default")
      (node (ref "U12") (pin "VIN") (pinfunction "VIN_VIN") (pintype "bidirectional"))
    )
    (net (code "67") (name "~{BAT1_CE}") (class "Default")
      (node (ref "B1") (pin "A4") (pinfunction "~{BAT_CE}_A4") (pintype "bidirectional"))
      (node (ref "SYSTEM") (pin "P$5") (pinfunction "5_P$5") (pintype "passive"))
      (node (ref "U12") (pin "D2") (pinfunction "D2_D2") (pintype "bidirectional"))
    )
    (net (code "68") (name "~{BAT2_CE}") (class "Default")
      (node (ref "B2") (pin "A4") (pinfunction "~{BAT_CE}_A4") (pintype "bidirectional"))
      (node (ref "SYSTEM") (pin "P$6") (pinfunction "6_P$6") (pintype "passive"))
      (node (ref "U12") (pin "D3") (pinfunction "D3_D3") (pintype "bidirectional"))
    )
    (net (code "69") (name "~{I2C_RST}") (class "Default")
      (node (ref "R58") (pin "2") (pinfunction "2_2") (pintype "passive"))
      (node (ref "SYSTEM") (pin "P$10") (pinfunction "10_P$10") (pintype "passive"))
      (node (ref "U12") (pin "D1") (pinfunction "D1_D1") (pintype "bidirectional"))
      (node (ref "U5") (pin "3") (pinfunction "RST_3") (pintype "bidirectional"))
    )
  )
)
